# 3__schdoc.net
KiCad netlist of a schematic drawn in Altium Designer
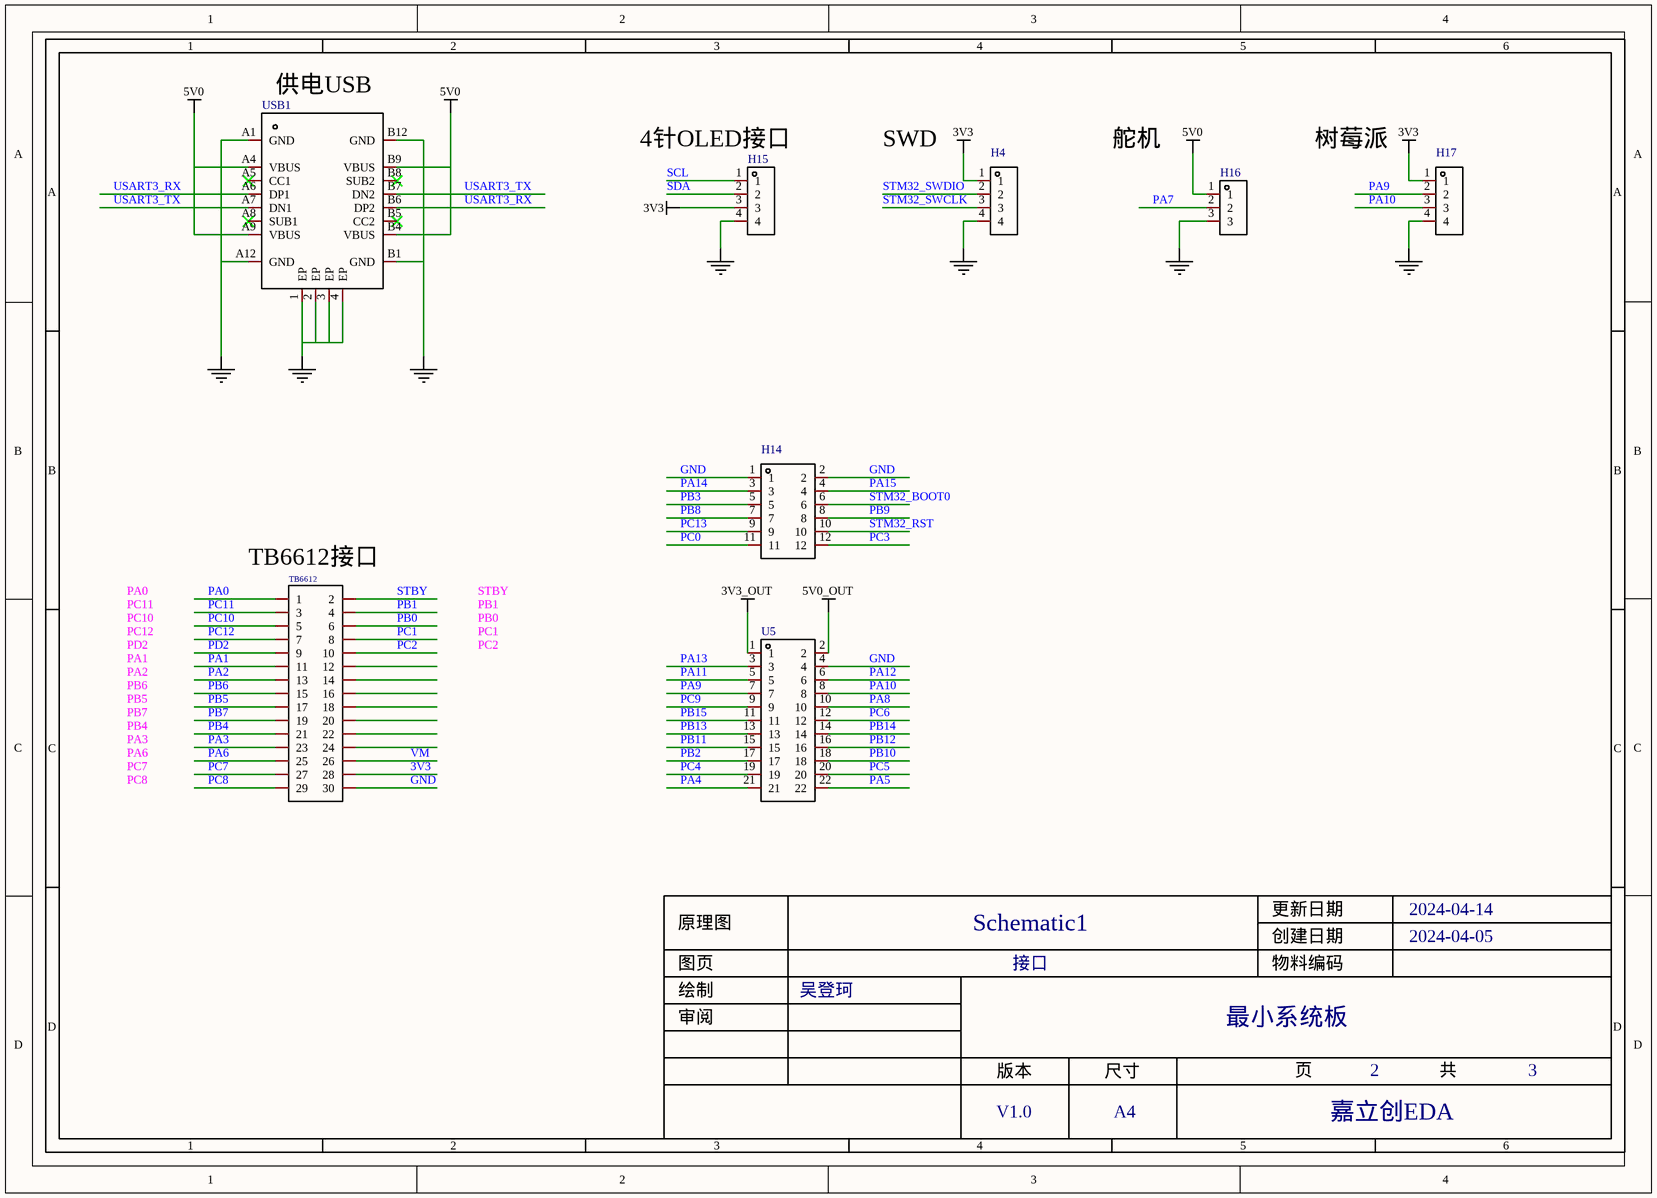
[diagram p0: 3_接口.schdoc.schdoc]

(export (version "E")
  (design (tool "Eeschema 10.0.6"))
  (components
    (comp (ref "H4")
      (value "PZ254V-11-04P")
      (fields (field (name "MANUFACTURER") "XFCN(兴飞)"))
      (libsource (lib "altium-import") (part "root_0_PZ254V-11-04P_"))
    )
    (comp (ref "H14")
      (value "HDR-M_2.54_2x6")
      (libsource (lib "altium-import") (part "root_0_HDR-M_2.54_2x6_"))
    )
    (comp (ref "H15")
      (value "HDR-M_2.54_1x4P")
      (libsource (lib "altium-import") (part "root_0_HDR-M_2.54_1x4P_"))
    )
    (comp (ref "H16")
      (value "HDR-F_2.54_1x3P")
      (libsource (lib "altium-import") (part "root_0_HDR-F_2.54_1x3P_"))
    )
    (comp (ref "H17")
      (value "HDR-F_2.54_1x4P")
      (fields (field (name "MANUFACTURER") "BOOMELE(博穆精密)") (field (name "MANUFACTURER PART") "2.54-1*4P母"))
      (libsource (lib "altium-import") (part "root_0_HDR-F_2.54_1x4P_"))
    )
    (comp (ref "TB6612")
      (value "2.54-2*15P双排针")
      (fields (field (name "MANUFACTURER") "BOOMELE(博穆精密)"))
      (libsource (lib "altium-import") (part "root_0_2.54-2*15P双排针_"))
    )
    (comp (ref "U5")
      (value "PM254-2-11-Z-8.5")
      (fields (field (name "MANUFACTURER") "HCTL(华灿天禄)"))
      (libsource (lib "altium-import") (part "root_0_PM254-2-11-Z-8.5_"))
    )
    (comp (ref "USB1")
      (value "KH-TYPE-C-16P")
      (description "连接器类型:Type-C;标准:-;公母:母;端口数量:1;触点数量:16P;安装方式:卧贴;额定电流 - 电源:3A;工作温度范围:-40℃~+85℃;")
      (fields (field (name "MANUFACTURER") "kinghelm(金航标)"))
      (libsource (lib "altium-import") (part "root_0_KH-TYPE-C-16P_"))
    )
  )
  (nets
    (net (code "1") (name "/GND") (class "Default")
      (node (ref "H14") (pin "1") (pinfunction "1_1") (pintype "passive"))
      (node (ref "H14") (pin "2") (pinfunction "2_2") (pintype "passive"))
      (node (ref "TB6612") (pin "30") (pinfunction "30_30") (pintype "passive"))
      (node (ref "U5") (pin "4") (pinfunction "4_4") (pintype "passive"))
    )
    (net (code "2") (name "/PA0") (class "Default")
      (node (ref "TB6612") (pin "1") (pinfunction "1_1") (pintype "passive"))
    )
    (net (code "3") (name "/PA1") (class "Default")
      (node (ref "TB6612") (pin "11") (pinfunction "11_11") (pintype "passive"))
    )
    (net (code "4") (name "/PA2") (class "Default")
      (node (ref "TB6612") (pin "13") (pinfunction "13_13") (pintype "passive"))
    )
    (net (code "5") (name "/PA3") (class "Default")
      (node (ref "TB6612") (pin "23") (pinfunction "23_23") (pintype "passive"))
    )
    (net (code "6") (name "/PA4") (class "Default")
      (node (ref "U5") (pin "21") (pinfunction "21_21") (pintype "passive"))
    )
    (net (code "7") (name "/PA5") (class "Default")
      (node (ref "U5") (pin "22") (pinfunction "22_22") (pintype "passive"))
    )
    (net (code "8") (name "/PA6") (class "Default")
      (node (ref "TB6612") (pin "25") (pinfunction "25_25") (pintype "passive"))
    )
    (net (code "9") (name "/PA7") (class "Default")
      (node (ref "H16") (pin "2") (pinfunction "2_2") (pintype "passive"))
    )
    (net (code "10") (name "/PA8") (class "Default")
      (node (ref "U5") (pin "10") (pinfunction "10_10") (pintype "passive"))
    )
    (net (code "11") (name "/PA9") (class "Default")
      (node (ref "H17") (pin "2") (pinfunction "2_2") (pintype "passive"))
      (node (ref "U5") (pin "7") (pinfunction "7_7") (pintype "passive"))
    )
    (net (code "12") (name "/PA10") (class "Default")
      (node (ref "H17") (pin "3") (pinfunction "3_3") (pintype "passive"))
      (node (ref "U5") (pin "8") (pinfunction "8_8") (pintype "passive"))
    )
    (net (code "13") (name "/PA11") (class "Default")
      (node (ref "U5") (pin "5") (pinfunction "5_5") (pintype "passive"))
    )
    (net (code "14") (name "/PA12") (class "Default")
      (node (ref "U5") (pin "6") (pinfunction "6_6") (pintype "passive"))
    )
    (net (code "15") (name "/PA13") (class "Default")
      (node (ref "U5") (pin "3") (pinfunction "3_3") (pintype "passive"))
    )
    (net (code "16") (name "/PA14") (class "Default")
      (node (ref "H14") (pin "3") (pinfunction "3_3") (pintype "passive"))
    )
    (net (code "17") (name "/PA15") (class "Default")
      (node (ref "H14") (pin "4") (pinfunction "4_4") (pintype "passive"))
    )
    (net (code "18") (name "/PB0") (class "Default")
      (node (ref "TB6612") (pin "6") (pinfunction "6_6") (pintype "passive"))
    )
    (net (code "19") (name "/PB1") (class "Default")
      (node (ref "TB6612") (pin "4") (pinfunction "4_4") (pintype "passive"))
    )
    (net (code "20") (name "/PB2") (class "Default")
      (node (ref "U5") (pin "17") (pinfunction "17_17") (pintype "passive"))
    )
    (net (code "21") (name "/PB3") (class "Default")
      (node (ref "H14") (pin "5") (pinfunction "5_5") (pintype "passive"))
    )
    (net (code "22") (name "/PB4") (class "Default")
      (node (ref "TB6612") (pin "21") (pinfunction "21_21") (pintype "passive"))
    )
    (net (code "23") (name "/PB5") (class "Default")
      (node (ref "TB6612") (pin "17") (pinfunction "17_17") (pintype "passive"))
    )
    (net (code "24") (name "/PB6") (class "Default")
      (node (ref "TB6612") (pin "15") (pinfunction "15_15") (pintype "passive"))
    )
    (net (code "25") (name "/PB7") (class "Default")
      (node (ref "TB6612") (pin "19") (pinfunction "19_19") (pintype "passive"))
    )
    (net (code "26") (name "/PB8") (class "Default")
      (node (ref "H14") (pin "7") (pinfunction "7_7") (pintype "passive"))
    )
    (net (code "27") (name "/PB9") (class "Default")
      (node (ref "H14") (pin "8") (pinfunction "8_8") (pintype "passive"))
    )
    (net (code "28") (name "/PB10") (class "Default")
      (node (ref "U5") (pin "18") (pinfunction "18_18") (pintype "passive"))
    )
    (net (code "29") (name "/PB11") (class "Default")
      (node (ref "U5") (pin "15") (pinfunction "15_15") (pintype "passive"))
    )
    (net (code "30") (name "/PB12") (class "Default")
      (node (ref "U5") (pin "16") (pinfunction "16_16") (pintype "passive"))
    )
    (net (code "31") (name "/PB13") (class "Default")
      (node (ref "U5") (pin "13") (pinfunction "13_13") (pintype "passive"))
    )
    (net (code "32") (name "/PB14") (class "Default")
      (node (ref "U5") (pin "14") (pinfunction "14_14") (pintype "passive"))
    )
    (net (code "33") (name "/PB15") (class "Default")
      (node (ref "U5") (pin "11") (pinfunction "11_11") (pintype "passive"))
    )
    (net (code "34") (name "/PC0") (class "Default")
      (node (ref "H14") (pin "11") (pinfunction "11_11") (pintype "passive"))
    )
    (net (code "35") (name "/PC1") (class "Default")
      (node (ref "TB6612") (pin "8") (pinfunction "8_8") (pintype "passive"))
    )
    (net (code "36") (name "/PC2") (class "Default")
      (node (ref "TB6612") (pin "10") (pinfunction "10_10") (pintype "passive"))
    )
    (net (code "37") (name "/PC3") (class "Default")
      (node (ref "H14") (pin "12") (pinfunction "12_12") (pintype "passive"))
    )
    (net (code "38") (name "/PC4") (class "Default")
      (node (ref "U5") (pin "19") (pinfunction "19_19") (pintype "passive"))
    )
    (net (code "39") (name "/PC5") (class "Default")
      (node (ref "U5") (pin "20") (pinfunction "20_20") (pintype "passive"))
    )
    (net (code "40") (name "/PC6") (class "Default")
      (node (ref "U5") (pin "12") (pinfunction "12_12") (pintype "passive"))
    )
    (net (code "41") (name "/PC7") (class "Default")
      (node (ref "TB6612") (pin "27") (pinfunction "27_27") (pintype "passive"))
    )
    (net (code "42") (name "/PC8") (class "Default")
      (node (ref "TB6612") (pin "29") (pinfunction "29_29") (pintype "passive"))
    )
    (net (code "43") (name "/PC9") (class "Default")
      (node (ref "U5") (pin "9") (pinfunction "9_9") (pintype "passive"))
    )
    (net (code "44") (name "/PC10") (class "Default")
      (node (ref "TB6612") (pin "5") (pinfunction "5_5") (pintype "passive"))
    )
    (net (code "45") (name "/PC11") (class "Default")
      (node (ref "TB6612") (pin "3") (pinfunction "3_3") (pintype "passive"))
    )
    (net (code "46") (name "/PC12") (class "Default")
      (node (ref "TB6612") (pin "7") (pinfunction "7_7") (pintype "passive"))
    )
    (net (code "47") (name "/PC13") (class "Default")
      (node (ref "H14") (pin "9") (pinfunction "9_9") (pintype "passive"))
    )
    (net (code "48") (name "/PD2") (class "Default")
      (node (ref "TB6612") (pin "9") (pinfunction "9_9") (pintype "passive"))
    )
    (net (code "49") (name "/SCL") (class "Default")
      (node (ref "H15") (pin "1") (pinfunction "1_1") (pintype "passive"))
    )
    (net (code "50") (name "/SDA") (class "Default")
      (node (ref "H15") (pin "2") (pinfunction "2_2") (pintype "passive"))
    )
    (net (code "51") (name "/STBY") (class "Default")
      (node (ref "TB6612") (pin "2") (pinfunction "2_2") (pintype "passive"))
    )
    (net (code "52") (name "/STM32_BOOT0") (class "Default")
      (node (ref "H14") (pin "6") (pinfunction "6_6") (pintype "passive"))
    )
    (net (code "53") (name "/STM32_RST") (class "Default")
      (node (ref "H14") (pin "10") (pinfunction "10_10") (pintype "passive"))
    )
    (net (code "54") (name "/STM32_SWCLK") (class "Default")
      (node (ref "H4") (pin "3") (pinfunction "3_3") (pintype "passive"))
    )
    (net (code "55") (name "/STM32_SWDIO") (class "Default")
      (node (ref "H4") (pin "2") (pinfunction "2_2") (pintype "passive"))
    )
    (net (code "56") (name "/USART3_RX") (class "Default")
      (node (ref "USB1") (pin "A6") (pinfunction "DP1_A6") (pintype "passive"))
      (node (ref "USB1") (pin "B6") (pinfunction "DP2_B6") (pintype "passive"))
    )
    (net (code "57") (name "/USART3_TX") (class "Default")
      (node (ref "USB1") (pin "A7") (pinfunction "DN1_A7") (pintype "passive"))
      (node (ref "USB1") (pin "B7") (pinfunction "DN2_B7") (pintype "passive"))
    )
    (net (code "58") (name "/VM") (class "Default")
      (node (ref "TB6612") (pin "26") (pinfunction "26_26") (pintype "passive"))
    )
    (net (code "59") (name "3V3") (class "Default")
      (node (ref "H15") (pin "3") (pinfunction "3_3") (pintype "passive"))
      (node (ref "H17") (pin "1") (pinfunction "1_1") (pintype "passive"))
      (node (ref "H4") (pin "1") (pinfunction "1_1") (pintype "passive"))
      (node (ref "TB6612") (pin "28") (pinfunction "28_28") (pintype "passive"))
    )
    (net (code "60") (name "3V3_OUT") (class "Default")
      (node (ref "U5") (pin "1") (pinfunction "1_1") (pintype "passive"))
    )
    (net (code "61") (name "5V0") (class "Default")
      (node (ref "H16") (pin "1") (pinfunction "1_1") (pintype "passive"))
      (node (ref "USB1") (pin "A4") (pinfunction "VBUS_A4") (pintype "passive"))
      (node (ref "USB1") (pin "A9") (pinfunction "VBUS_A9") (pintype "passive"))
      (node (ref "USB1") (pin "B4") (pinfunction "VBUS_B4") (pintype "passive"))
      (node (ref "USB1") (pin "B9") (pinfunction "VBUS_B9") (pintype "passive"))
    )
    (net (code "62") (name "5V0_OUT") (class "Default")
      (node (ref "U5") (pin "2") (pinfunction "2_2") (pintype "passive"))
    )
    (net (code "63") (name "<NO NET>") (class "Default")
      (node (ref "H15") (pin "4") (pinfunction "4_4") (pintype "passive"))
      (node (ref "H16") (pin "3") (pinfunction "3_3") (pintype "passive"))
      (node (ref "H17") (pin "4") (pinfunction "4_4") (pintype "passive"))
      (node (ref "H4") (pin "4") (pinfunction "4_4") (pintype "passive"))
      (node (ref "USB1") (pin "1") (pinfunction "EP_1") (pintype "passive"))
      (node (ref "USB1") (pin "2") (pinfunction "EP_2") (pintype "passive"))
      (node (ref "USB1") (pin "3") (pinfunction "EP_3") (pintype "passive"))
      (node (ref "USB1") (pin "4") (pinfunction "EP_4") (pintype "passive"))
      (node (ref "USB1") (pin "A1") (pinfunction "GND_A1") (pintype "passive"))
      (node (ref "USB1") (pin "A12") (pinfunction "GND_A12") (pintype "passive"))
      (node (ref "USB1") (pin "B1") (pinfunction "GND_B1") (pintype "passive"))
      (node (ref "USB1") (pin "B12") (pinfunction "GND_B12") (pintype "passive"))
    )
    (net (code "64") (name "unconnected-(TB6612-Pad12)") (class "Default")
      (node (ref "TB6612") (pin "12") (pinfunction "12_12") (pintype "passive"))
    )
    (net (code "65") (name "unconnected-(TB6612-Pad14)") (class "Default")
      (node (ref "TB6612") (pin "14") (pinfunction "14_14") (pintype "passive"))
    )
    (net (code "66") (name "unconnected-(TB6612-Pad16)") (class "Default")
      (node (ref "TB6612") (pin "16") (pinfunction "16_16") (pintype "passive"))
    )
    (net (code "67") (name "unconnected-(TB6612-Pad18)") (class "Default")
      (node (ref "TB6612") (pin "18") (pinfunction "18_18") (pintype "passive"))
    )
    (net (code "68") (name "unconnected-(TB6612-Pad20)") (class "Default")
      (node (ref "TB6612") (pin "20") (pinfunction "20_20") (pintype "passive"))
    )
    (net (code "69") (name "unconnected-(TB6612-Pad22)") (class "Default")
      (node (ref "TB6612") (pin "22") (pinfunction "22_22") (pintype "passive"))
    )
    (net (code "70") (name "unconnected-(TB6612-Pad24)") (class "Default")
      (node (ref "TB6612") (pin "24") (pinfunction "24_24") (pintype "passive"))
    )
    (net (code "71") (name "unconnected-(USB1-CC1-PadA5)") (class "Default")
      (node (ref "USB1") (pin "A5") (pinfunction "CC1_A5") (pintype "passive+no_connect"))
    )
    (net (code "72") (name "unconnected-(USB1-CC2-PadB5)") (class "Default")
      (node (ref "USB1") (pin "B5") (pinfunction "CC2_B5") (pintype "passive+no_connect"))
    )
    (net (code "73") (name "unconnected-(USB1-SUB1-PadA8)") (class "Default")
      (node (ref "USB1") (pin "A8") (pinfunction "SUB1_A8") (pintype "passive+no_connect"))
    )
    (net (code "74") (name "unconnected-(USB1-SUB2-PadB8)") (class "Default")
      (node (ref "USB1") (pin "B8") (pinfunction "SUB2_B8") (pintype "passive+no_connect"))
    )
  )
)
